# Power.net
KiCad netlist of a schematic drawn in Altium Designer
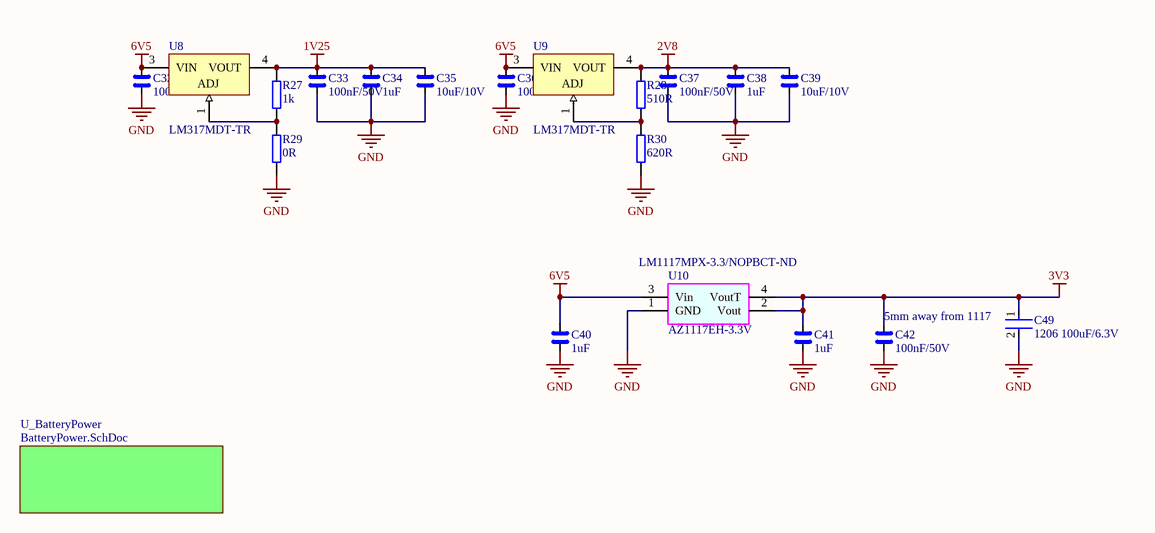
[diagram p0: Power.SchDoc]

(export (version "E")
  (design (tool "Eeschema 10.0.6"))
  (components
    (comp (ref "C32")
      (value "100nF/50V")
      (footprint "1608[0603]")
      (description "Cap Ceramic 0.1uF 50V X7R 20% SMD 0603 125C Paper T/R")
      (fields (field (name "LCSCPARTNO") "C14663"))
      (libsource (lib "Sch") (part "C"))
    )
    (comp (ref "C33")
      (value "100nF/50V")
      (footprint "1608[0603]")
      (description "Cap Ceramic 0.1uF 50V X7R 20% SMD 0603 125C Paper T/R")
      (fields (field (name "LCSCPARTNO") "C14663"))
      (libsource (lib "Sch") (part "C"))
    )
    (comp (ref "C34")
      (value "1uF")
      (footprint "1608[0603]")
      (description "CAP CER 1UF 10V X5R 0603")
      (fields (field (name "LCSCPARTNO") "C15849"))
      (libsource (lib "Sch") (part "C"))
    )
    (comp (ref "C35")
      (value "10uF/10V")
      (footprint "1608[0603]")
      (description "Capacitor")
      (fields (field (name "LCSCPARTNO") "C19702"))
      (libsource (lib "Sch") (part "C"))
    )
    (comp (ref "C36")
      (value "100nF/50V")
      (footprint "1608[0603]")
      (description "Cap Ceramic 0.1uF 50V X7R 20% SMD 0603 125C Paper T/R")
      (fields (field (name "LCSCPARTNO") "C14663"))
      (libsource (lib "Sch") (part "C"))
    )
    (comp (ref "C37")
      (value "100nF/50V")
      (footprint "1608[0603]")
      (description "Cap Ceramic 0.1uF 50V X7R 20% SMD 0603 125C Paper T/R")
      (fields (field (name "LCSCPARTNO") "C14663"))
      (libsource (lib "Sch") (part "C"))
    )
    (comp (ref "C38")
      (value "1uF")
      (footprint "1608[0603]")
      (description "CAP CER 1UF 10V X5R 0603")
      (fields (field (name "LCSCPARTNO") "C15849"))
      (libsource (lib "Sch") (part "C"))
    )
    (comp (ref "C39")
      (value "10uF/10V")
      (footprint "1608[0603]")
      (description "Capacitor")
      (fields (field (name "LCSCPARTNO") "C19702"))
      (libsource (lib "Sch") (part "C"))
    )
    (comp (ref "C40")
      (value "1uF")
      (footprint "1608[0603]")
      (description "CAP CER 1UF 10V X5R 0603")
      (fields (field (name "LCSCPARTNO") "C15849"))
      (libsource (lib "Sch") (part "C"))
    )
    (comp (ref "C41")
      (value "1uF")
      (footprint "1608[0603]")
      (description "CAP CER 1UF 10V X5R 0603")
      (fields (field (name "LCSCPARTNO") "C15849"))
      (libsource (lib "Sch") (part "C"))
    )
    (comp (ref "C42")
      (value "100nF/50V")
      (footprint "1608[0603]")
      (description "Cap Ceramic 0.1uF 50V X7R 20% SMD 0603 125C Paper T/R")
      (fields (field (name "LCSCPARTNO") "C14663"))
      (libsource (lib "Sch") (part "C"))
    )
    (comp (ref "C49")
      (value "1206 100uF/6.3V")
      (footprint "FP-CL31-IPC_B")
      (description "Cap Ceramic 100uF 6.3V X5R ±20% SMD 1206 +85°C Embossed T/R")
      (fields (field (name "LCSCPARTNO") "C15008"))
      (libsource (lib "Altium Content Vault") (part "b4654b650e69147ec39a6b967a45e02"))
    )
    (comp (ref "R27")
      (value "1k")
      (footprint "1608[0603]")
      (description "Res General Purpose Thick Film 0603 1% 1/10W ±100ppm/°C Molded SMD Paper T/R")
      (fields (field (name "LCSCPARTNO") "C21190"))
      (libsource (lib "Sch") (part "R"))
    )
    (comp (ref "R28")
      (value "510R")
      (footprint "1608[0603]")
      (description "Res General Purpose Thick Film 0603 1% 1/10W ±100ppm/°C Molded SMD Paper T/R")
      (fields (field (name "LCSCPARTNO") "C23193"))
      (libsource (lib "Sch") (part "R"))
    )
    (comp (ref "R29")
      (value "0R")
      (footprint "1608[0603]")
      (description "Res General Purpose Thick Film 0603 1% 1/10W ±100ppm/°C Molded SMD Paper T/R")
      (fields (field (name "LCSCPARTNO") "C21189"))
      (libsource (lib "Sch") (part "R"))
    )
    (comp (ref "R30")
      (value "620R")
      (footprint "1608[0603]")
      (description "Res General Purpose Thick Film 0603 1% 1/10W ±100ppm/°C Molded SMD Paper T/R")
      (fields (field (name "LCSCPARTNO") "C23220"))
      (libsource (lib "Sch") (part "R"))
    )
    (comp (ref "U8")
      (value "LM317MDT-TR")
      (footprint "TO-252_M")
      (description "500mA, Medium Current 1.2 to 37 V Adjustable Voltage Regulator, 3-Pin DPAK, Tape and Reel")
      (fields (field (name "LCSCPARTNO") "C75510"))
      (libsource (lib "Altium Content Vault") (part "PM-REG-LM217M-SOT3"))
    )
    (comp (ref "U9")
      (value "LM317MDT-TR")
      (footprint "TO-252_M")
      (description "500mA, Medium Current 1.2 to 37 V Adjustable Voltage Regulator, 3-Pin DPAK, Tape and Reel")
      (fields (field (name "LCSCPARTNO") "C75510"))
      (libsource (lib "Altium Content Vault") (part "PM-REG-LM217M-SOT3"))
    )
    (comp (ref "U10")
      (value "AZ1117EH-3.3V")
      (footprint "SOT-223")
      (description "IC REG LIN 3.3V 800MA SOT223-4")
      (fields
        (field (name "SUPPLIER PART NUMBER 1") "LM1117MPX-3.3/NOPBCT-ND")
        (field (name "LCSCPARTNO") "C6186")
      )
      (libsource (lib "Sch") (part "AZ1117EH-3.3V"))
    )
  )
  (nets
    (net (code "1") (name "1V25") (class "Default")
      (node (ref "C33") (pin "1") (pinfunction "1_1") (pintype "passive"))
      (node (ref "C34") (pin "1") (pinfunction "1_1") (pintype "passive"))
      (node (ref "C35") (pin "1") (pinfunction "1_1") (pintype "passive"))
      (node (ref "R27") (pin "1") (pintype "passive"))
      (node (ref "U8") (pin "4") (pinfunction "VOUT_4") (pintype "power_in"))
    )
    (net (code "2") (name "2V8") (class "Default")
      (node (ref "C37") (pin "1") (pinfunction "1_1") (pintype "passive"))
      (node (ref "C38") (pin "1") (pinfunction "1_1") (pintype "passive"))
      (node (ref "C39") (pin "1") (pinfunction "1_1") (pintype "passive"))
      (node (ref "R28") (pin "1") (pintype "passive"))
      (node (ref "U9") (pin "4") (pinfunction "VOUT_4") (pintype "power_in"))
    )
    (net (code "3") (name "3V3") (class "Default")
      (node (ref "C41") (pin "1") (pinfunction "1_1") (pintype "passive"))
      (node (ref "C42") (pin "1") (pinfunction "1_1") (pintype "passive"))
      (node (ref "C49") (pin "1") (pinfunction "1_1") (pintype "passive"))
      (node (ref "U10") (pin "2") (pinfunction "Vout_2") (pintype "passive"))
      (node (ref "U10") (pin "4") (pinfunction "VoutT_4") (pintype "passive"))
    )
    (net (code "4") (name "6V5") (class "Default")
      (node (ref "C32") (pin "1") (pinfunction "1_1") (pintype "passive"))
      (node (ref "C36") (pin "1") (pinfunction "1_1") (pintype "passive"))
      (node (ref "C40") (pin "1") (pinfunction "1_1") (pintype "passive"))
      (node (ref "U10") (pin "3") (pinfunction "Vin_3") (pintype "passive"))
      (node (ref "U8") (pin "3") (pinfunction "VIN_3") (pintype "power_in"))
      (node (ref "U9") (pin "3") (pinfunction "VIN_3") (pintype "power_in"))
    )
    (net (code "5") (name "GND") (class "Default")
      (node (ref "C32") (pin "2") (pinfunction "2_2") (pintype "passive"))
      (node (ref "C33") (pin "2") (pinfunction "2_2") (pintype "passive"))
      (node (ref "C34") (pin "2") (pinfunction "2_2") (pintype "passive"))
      (node (ref "C35") (pin "2") (pinfunction "2_2") (pintype "passive"))
      (node (ref "C36") (pin "2") (pinfunction "2_2") (pintype "passive"))
      (node (ref "C37") (pin "2") (pinfunction "2_2") (pintype "passive"))
      (node (ref "C38") (pin "2") (pinfunction "2_2") (pintype "passive"))
      (node (ref "C39") (pin "2") (pinfunction "2_2") (pintype "passive"))
      (node (ref "C40") (pin "2") (pinfunction "2_2") (pintype "passive"))
      (node (ref "C41") (pin "2") (pinfunction "2_2") (pintype "passive"))
      (node (ref "C42") (pin "2") (pinfunction "2_2") (pintype "passive"))
      (node (ref "C49") (pin "2") (pinfunction "2_2") (pintype "passive"))
      (node (ref "R29") (pin "2") (pintype "passive"))
      (node (ref "R30") (pin "2") (pintype "passive"))
      (node (ref "U10") (pin "1") (pinfunction "GND_1") (pintype "power_in"))
    )
    (net (code "6") (name "Net-(U8-ADJ)") (class "Default")
      (node (ref "R27") (pin "2") (pintype "passive"))
      (node (ref "R29") (pin "1") (pintype "passive"))
      (node (ref "U8") (pin "1") (pinfunction "ADJ_1") (pintype "input"))
    )
    (net (code "7") (name "Net-(U9-ADJ)") (class "Default")
      (node (ref "R28") (pin "2") (pintype "passive"))
      (node (ref "R30") (pin "1") (pintype "passive"))
      (node (ref "U9") (pin "1") (pinfunction "ADJ_1") (pintype "input"))
    )
  )
)
